# LM5116.net
KiCad netlist of a schematic drawn in Altium Designer
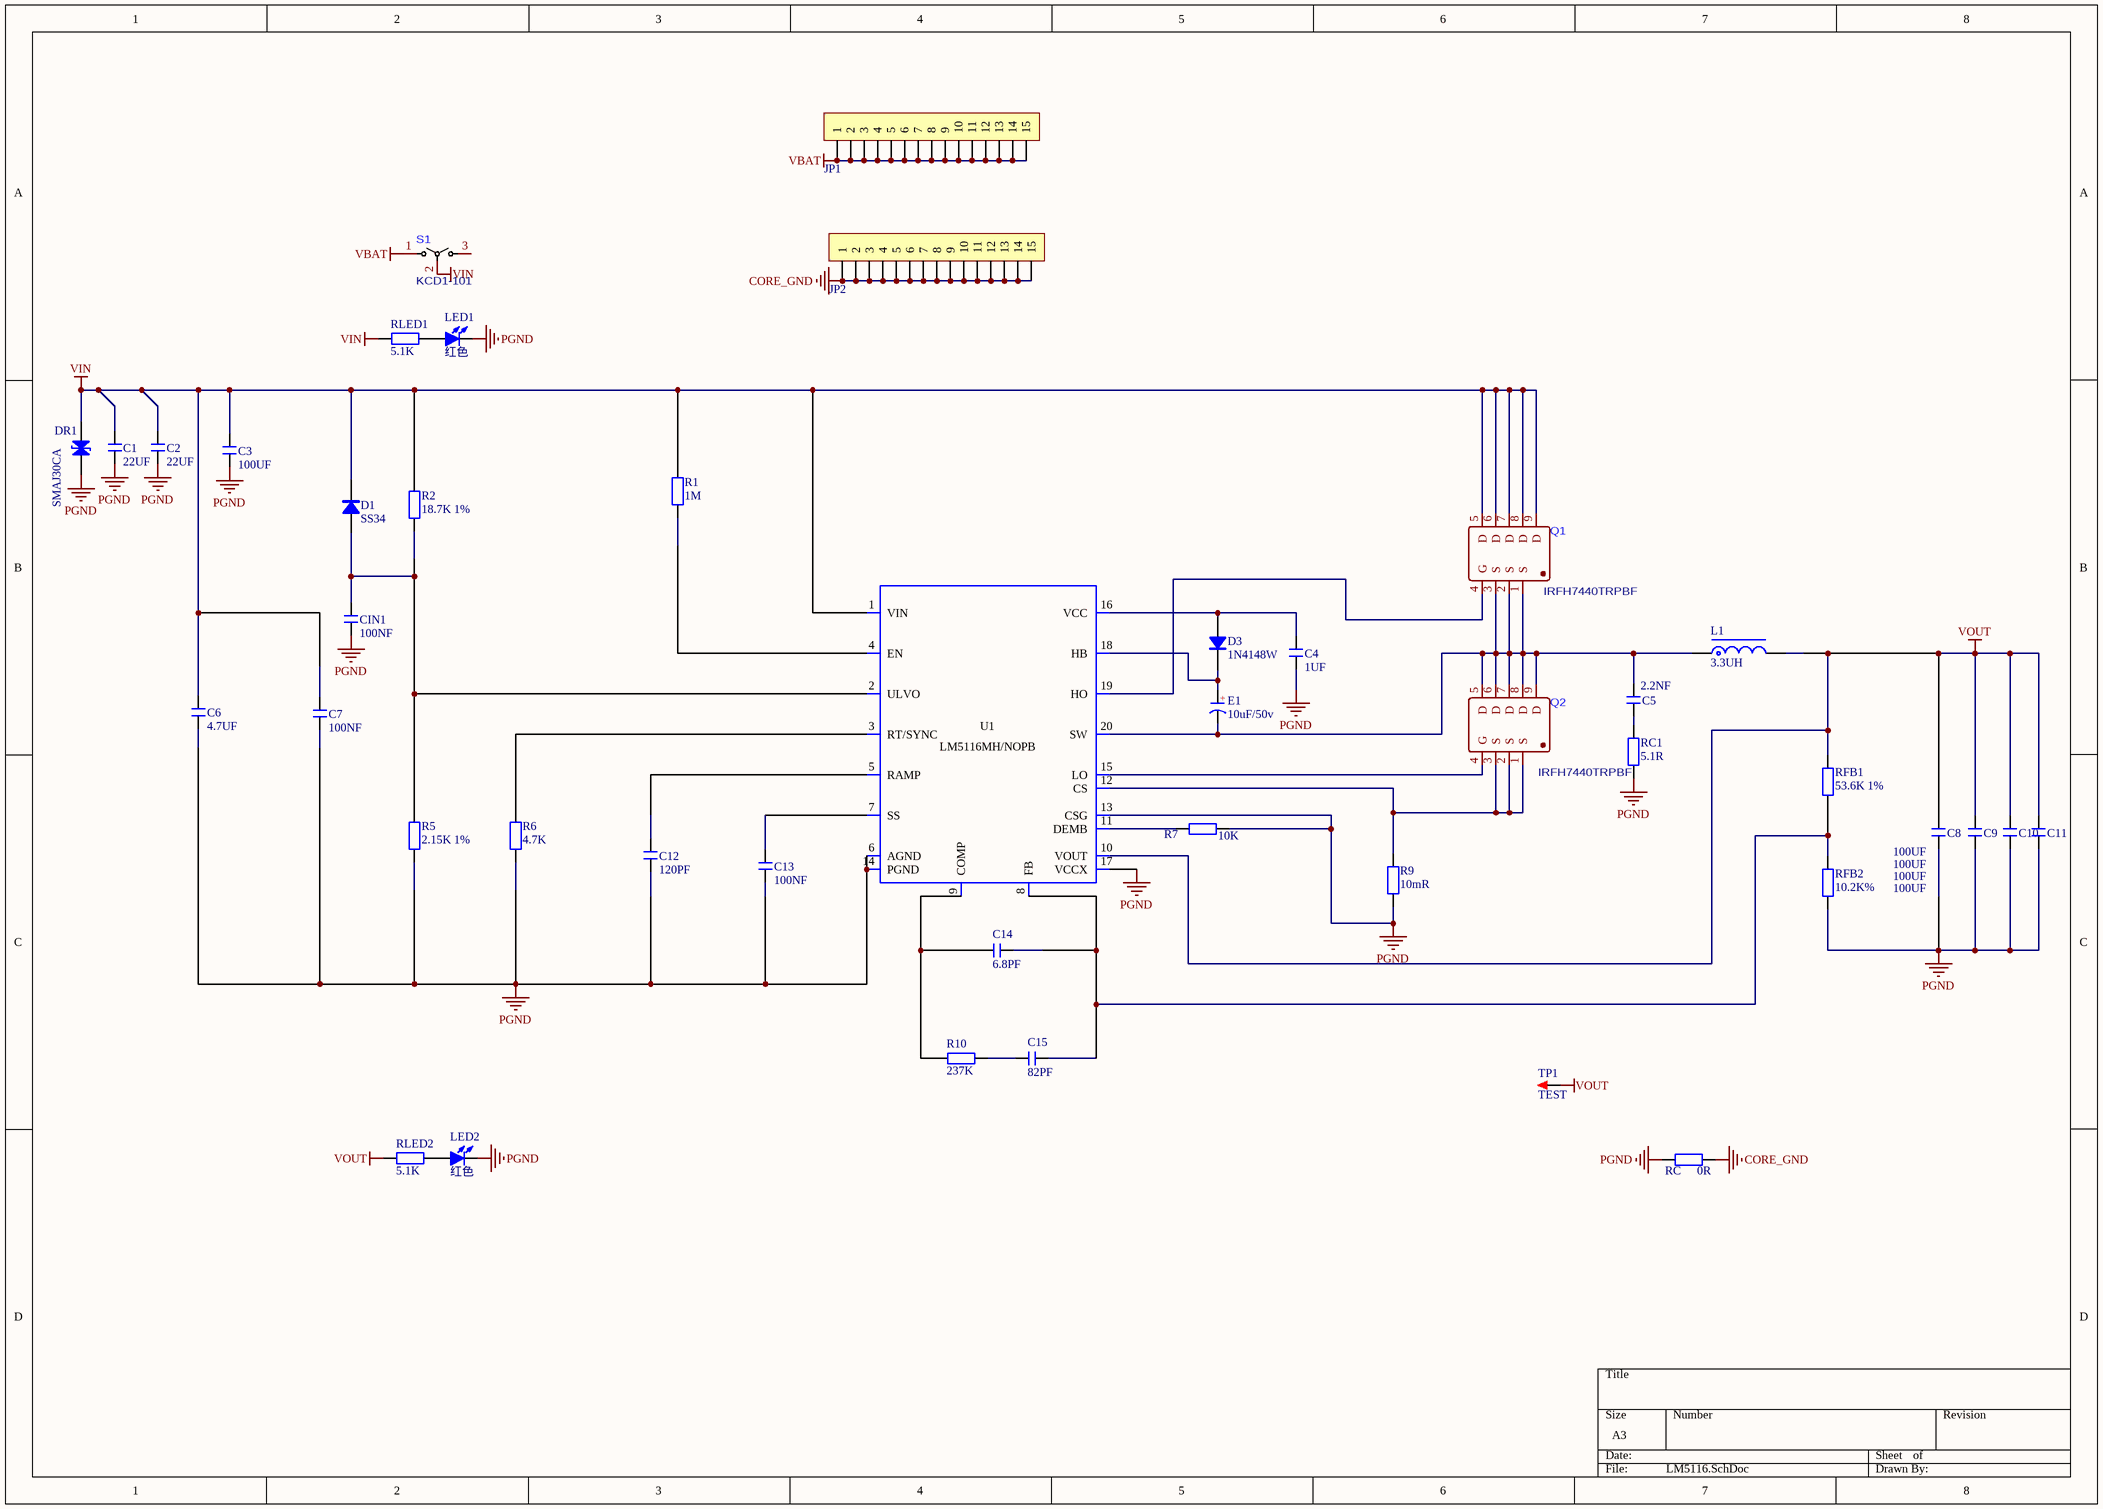
[diagram p0: LM5116.SchDoc]

(export (version "E")
  (design (tool "Eeschema 10.0.6"))
  (components
    (comp (ref "C1")
      (value "22UF")
      (footprint "C 1206_L")
      (description "无极性贴片电容")
      (fields (field (name "版权归属") "源创客"))
      (libsource (lib "3.1   - 电阻-电容-电感") (part "C"))
    )
    (comp (ref "C2")
      (value "22UF")
      (footprint "C 1206_L")
      (description "无极性贴片电容")
      (fields (field (name "版权归属") "源创客"))
      (libsource (lib "3.1   - 电阻-电容-电感") (part "C"))
    )
    (comp (ref "C3")
      (value "100UF")
      (footprint "C 1210_L")
      (description "无极性贴片电容")
      (fields (field (name "版权归属") "源创客"))
      (libsource (lib "3.1   - 电阻-电容-电感") (part "C"))
    )
    (comp (ref "C4")
      (value "1UF")
      (footprint "C 0805_L")
      (description "无极性贴片电容")
      (fields (field (name "版权归属") "源创客"))
      (libsource (lib "3.1   - 电阻-电容-电感") (part "C"))
    )
    (comp (ref "C5")
      (value "2.2NF")
      (footprint "C 0805_L")
      (description "无极性贴片电容")
      (fields (field (name "版权归属") "源创客"))
      (libsource (lib "3.1   - 电阻-电容-电感") (part "C"))
    )
    (comp (ref "C6")
      (value "4.7UF")
      (footprint "C 0805_L")
      (description "无极性贴片电容")
      (fields (field (name "版权归属") "源创客"))
      (libsource (lib "3.1   - 电阻-电容-电感") (part "C"))
    )
    (comp (ref "C7")
      (value "100NF")
      (footprint "C 0805_L")
      (description "无极性贴片电容")
      (fields (field (name "版权归属") "源创客"))
      (libsource (lib "3.1   - 电阻-电容-电感") (part "C"))
    )
    (comp (ref "C8")
      (value "100UF")
      (footprint "C 1210_L")
      (description "无极性贴片电容")
      (fields (field (name "版权归属") "源创客"))
      (libsource (lib "3.1   - 电阻-电容-电感") (part "C"))
    )
    (comp (ref "C9")
      (value "100UF")
      (footprint "C 1210_L")
      (description "无极性贴片电容")
      (fields (field (name "版权归属") "源创客"))
      (libsource (lib "3.1   - 电阻-电容-电感") (part "C"))
    )
    (comp (ref "C10")
      (value "100UF")
      (footprint "C 1210_L")
      (description "无极性贴片电容")
      (fields (field (name "版权归属") "源创客"))
      (libsource (lib "3.1   - 电阻-电容-电感") (part "C"))
    )
    (comp (ref "C11")
      (value "100UF")
      (footprint "C 1210_L")
      (description "无极性贴片电容")
      (fields (field (name "版权归属") "源创客"))
      (libsource (lib "3.1   - 电阻-电容-电感") (part "C"))
    )
    (comp (ref "C12")
      (value "120PF")
      (footprint "C 0805_L")
      (description "无极性贴片电容")
      (fields (field (name "版权归属") "源创客"))
      (libsource (lib "3.1   - 电阻-电容-电感") (part "C"))
    )
    (comp (ref "C13")
      (value "100NF")
      (footprint "C 0805_L")
      (description "无极性贴片电容")
      (fields (field (name "版权归属") "源创客"))
      (libsource (lib "3.1   - 电阻-电容-电感") (part "C"))
    )
    (comp (ref "C14")
      (value "6.8PF")
      (footprint "C 0805_L")
      (description "无极性贴片电容")
      (fields (field (name "版权归属") "源创客"))
      (libsource (lib "3.1   - 电阻-电容-电感") (part "C"))
    )
    (comp (ref "C15")
      (value "82PF")
      (footprint "C 0805_L")
      (description "无极性贴片电容")
      (fields (field (name "版权归属") "源创客"))
      (libsource (lib "3.1   - 电阻-电容-电感") (part "C"))
    )
    (comp (ref "CIN1")
      (value "100NF")
      (footprint "C 0805_L")
      (description "无极性贴片电容")
      (fields (field (name "版权归属") "源创客"))
      (libsource (lib "3.1   - 电阻-电容-电感") (part "C"))
    )
    (comp (ref "D1")
      (value "SS34")
      (footprint "SMA")
      (description "肖特基二极管")
      (fields (field (name "版权归属") "源创客"))
      (libsource (lib "8.1   - 二极管-整流桥") (part "SS34"))
    )
    (comp (ref "D3")
      (value "1N4148W")
      (footprint "SOD-123")
      (description "肖特基二极管")
      (fields (field (name "版权归属") "源创客"))
      (libsource (lib "8.1   - 二极管-整流桥") (part "SS34"))
    )
    (comp (ref "DR1")
      (value "SMAJ30CA")
      (footprint "SMA")
      (description "瞬态电压抑制二极管")
      (fields (field (name "版权归属") "源创客"))
      (libsource (lib "8.1   - 二极管-整流桥") (part "DR"))
    )
    (comp (ref "E1")
      (value "10uF/50v")
      (footprint "CAP 2.5*5*11-H")
      (description "直插电解电容")
      (fields (field (name "版权归属") "源创客"))
      (libsource (lib "3.1   - 电阻-电容-电感") (part "C-CAP"))
    )
    (comp (ref "JP1")
      (value "HDR-1X15")
      (footprint "HDR2.54-LI-15P")
      (description "15P接插件")
      (fields (field (name "版权归属") "源创客"))
      (libsource (lib "4.6   - 接插件-脚距2.54") (part "Header 15"))
    )
    (comp (ref "JP2")
      (value "HDR-1X15")
      (footprint "HDR2.54-LI-15P")
      (description "15P接插件")
      (fields (field (name "版权归属") "源创客"))
      (libsource (lib "4.6   - 接插件-脚距2.54") (part "Header 15"))
    )
    (comp (ref "L1")
      (value "3.3UH")
      (footprint "SMD-L-1770")
      (description "贴片功率电感")
      (fields (field (name "版权归属") "源创客"))
      (libsource (lib "3.1   - 电阻-电容-电感") (part "L-CD"))
    )
    (comp (ref "LED1")
      (value "红色")
      (footprint "LED 0805G")
      (description "贴片LED")
      (fields (field (name "版权归属") "源创客"))
      (libsource (lib "9.1   - LED") (part "LED-SMD"))
    )
    (comp (ref "LED2")
      (value "红色")
      (footprint "LED 0805G")
      (description "贴片LED")
      (fields (field (name "版权归属") "源创客"))
      (libsource (lib "9.1   - LED") (part "LED-SMD"))
    )
    (comp (ref "Q1")
      (value "IRFH7440TRPBF")
      (footprint "PQFN-8P_L5.8-W4.9-P1.27-LS6.0-BL")
      (libsource (lib "IRFH7440TRPBF") (part "IRFH7440TRPBF"))
    )
    (comp (ref "Q2")
      (value "IRFH7440TRPBF")
      (footprint "PQFN-8P_L5.8-W4.9-P1.27-LS6.0-BL")
      (libsource (lib "IRFH7440TRPBF") (part "IRFH7440TRPBF"))
    )
    (comp (ref "R1")
      (value "1M")
      (footprint "R 0805_L")
      (description "贴片电阻")
      (fields (field (name "版权归属") "源创客"))
      (libsource (lib "3.1   - 电阻-电容-电感") (part "R"))
    )
    (comp (ref "R2")
      (value "18.7K 1%")
      (footprint "R 0805_L")
      (description "贴片电阻")
      (fields (field (name "版权归属") "源创客"))
      (libsource (lib "3.1   - 电阻-电容-电感") (part "R"))
    )
    (comp (ref "R5")
      (value "2.15K 1%")
      (footprint "R 0805_L")
      (description "贴片电阻")
      (fields (field (name "版权归属") "源创客"))
      (libsource (lib "3.1   - 电阻-电容-电感") (part "R"))
    )
    (comp (ref "R6")
      (value "4.7K")
      (footprint "R 0805_L")
      (description "贴片电阻")
      (fields (field (name "版权归属") "源创客"))
      (libsource (lib "3.1   - 电阻-电容-电感") (part "R"))
    )
    (comp (ref "R7")
      (value "10K")
      (footprint "R 0805_L")
      (description "贴片电阻")
      (fields (field (name "版权归属") "源创客"))
      (libsource (lib "3.1   - 电阻-电容-电感") (part "R"))
    )
    (comp (ref "R9")
      (value "10mR")
      (footprint "R 1206_L")
      (description "贴片电阻")
      (fields (field (name "版权归属") "源创客"))
      (libsource (lib "3.1   - 电阻-电容-电感") (part "R"))
    )
    (comp (ref "R10")
      (value "237K")
      (footprint "R 0805_L")
      (description "贴片电阻")
      (fields (field (name "版权归属") "源创客"))
      (libsource (lib "3.1   - 电阻-电容-电感") (part "R"))
    )
    (comp (ref "RC")
      (value "0R")
      (footprint "R 0805_L")
      (description "贴片电阻")
      (fields (field (name "版权归属") "源创客"))
      (libsource (lib "3.1   - 电阻-电容-电感") (part "R"))
    )
    (comp (ref "RC1")
      (value "5.1R")
      (footprint "R 0805_L")
      (description "贴片电阻")
      (fields (field (name "版权归属") "源创客"))
      (libsource (lib "3.1   - 电阻-电容-电感") (part "R"))
    )
    (comp (ref "RFB1")
      (value "53.6K 1%")
      (footprint "R 0805_L")
      (description "贴片电阻")
      (fields (field (name "版权归属") "源创客"))
      (libsource (lib "3.1   - 电阻-电容-电感") (part "R"))
    )
    (comp (ref "RFB2")
      (value "10.2K%")
      (footprint "R 0805_L")
      (description "贴片电阻")
      (fields (field (name "版权归属") "源创客"))
      (libsource (lib "3.1   - 电阻-电容-电感") (part "R"))
    )
    (comp (ref "RLED1")
      (value "5.1K")
      (footprint "R 0805_L")
      (description "贴片电阻")
      (fields (field (name "版权归属") "源创客"))
      (libsource (lib "3.1   - 电阻-电容-电感") (part "R"))
    )
    (comp (ref "RLED2")
      (value "5.1K")
      (footprint "R 0805_L")
      (description "贴片电阻")
      (fields (field (name "版权归属") "源创客"))
      (libsource (lib "3.1   - 电阻-电容-电感") (part "R"))
    )
    (comp (ref "S1")
      (value "KCD1-101")
      (footprint "KEY-TH_CN-KCD1-101-3P")
      (libsource (lib "CN-KCD1-101-3P") (part "CN-KCD1-101-3P"))
    )
    (comp (ref "TP1")
      (value "TEST")
      (footprint "TEST 1.6")
      (description "测试点")
      (fields (field (name "版权归属") "源创客"))
      (libsource (lib "15.1 - 未分类器件") (part "TEST"))
    )
    (comp (ref "U1")
      (value "LM5116MH/NOPB")
      (footprint "HTSSOP-20_L6.5-W4.4-P0.65-LS6.4-BL-EP")
      (fields (field (name "PACKAGEREFERENCE") "LM5116MH/NOPB"))
      (libsource (lib "TI WEBENCH") (part "U1"))
    )
  )
  (nets
    (net (code "1") (name "CORE_GND") (class "Default")
      (node (ref "JP2") (pin "1") (pinfunction "1_1") (pintype "passive"))
      (node (ref "JP2") (pin "10") (pinfunction "10_10") (pintype "passive"))
      (node (ref "JP2") (pin "11") (pinfunction "11_11") (pintype "passive"))
      (node (ref "JP2") (pin "12") (pinfunction "12_12") (pintype "passive"))
      (node (ref "JP2") (pin "13") (pinfunction "13_13") (pintype "passive"))
      (node (ref "JP2") (pin "14") (pinfunction "14_14") (pintype "passive"))
      (node (ref "JP2") (pin "15") (pinfunction "15_15") (pintype "passive"))
      (node (ref "JP2") (pin "2") (pinfunction "2_2") (pintype "passive"))
      (node (ref "JP2") (pin "3") (pinfunction "3_3") (pintype "passive"))
      (node (ref "JP2") (pin "4") (pinfunction "4_4") (pintype "passive"))
      (node (ref "JP2") (pin "5") (pinfunction "5_5") (pintype "passive"))
      (node (ref "JP2") (pin "6") (pinfunction "6_6") (pintype "passive"))
      (node (ref "JP2") (pin "7") (pinfunction "7_7") (pintype "passive"))
      (node (ref "JP2") (pin "8") (pinfunction "8_8") (pintype "passive"))
      (node (ref "JP2") (pin "9") (pinfunction "9_9") (pintype "passive"))
      (node (ref "RC") (pin "1") (pinfunction "1_1") (pintype "passive"))
    )
    (net (code "2") (name "Net-(C5-Pad1)") (class "Default")
      (node (ref "C5") (pin "1") (pinfunction "1_1") (pintype "passive"))
      (node (ref "RC1") (pin "1") (pinfunction "1_1") (pintype "passive"))
    )
    (net (code "3") (name "Net-(C15-Pad1)") (class "Default")
      (node (ref "C15") (pin "1") (pinfunction "1_1") (pintype "passive"))
      (node (ref "R10") (pin "1") (pinfunction "1_1") (pintype "passive"))
    )
    (net (code "4") (name "Net-(D1-A)") (class "Default")
      (node (ref "CIN1") (pin "2") (pinfunction "2_2") (pintype "passive"))
      (node (ref "D1") (pin "1") (pinfunction "A_1") (pintype "passive"))
      (node (ref "R2") (pin "1") (pinfunction "1_1") (pintype "passive"))
      (node (ref "R5") (pin "2") (pinfunction "2_2") (pintype "passive"))
      (node (ref "U1") (pin "2") (pinfunction "ULVO_2") (pintype "passive"))
    )
    (net (code "5") (name "Net-(D3-A)") (class "Default")
      (node (ref "C4") (pin "2") (pinfunction "2_2") (pintype "passive"))
      (node (ref "D3") (pin "1") (pinfunction "A_1") (pintype "passive"))
      (node (ref "U1") (pin "16") (pinfunction "VCC_16") (pintype "passive"))
    )
    (net (code "6") (name "Net-(D3-K)") (class "Default")
      (node (ref "D3") (pin "2") (pinfunction "K_2") (pintype "passive"))
      (node (ref "E1") (pin "1") (pinfunction "A_1") (pintype "passive"))
      (node (ref "U1") (pin "18") (pinfunction "HB_18") (pintype "passive"))
    )
    (net (code "7") (name "Net-(E1-K)") (class "Default")
      (node (ref "C5") (pin "2") (pinfunction "2_2") (pintype "passive"))
      (node (ref "E1") (pin "2") (pinfunction "K_2") (pintype "passive"))
      (node (ref "L1") (pin "1") (pinfunction "1_1") (pintype "passive"))
      (node (ref "Q1") (pin "1") (pinfunction "S_1") (pintype "passive"))
      (node (ref "Q1") (pin "2") (pinfunction "S_2") (pintype "passive"))
      (node (ref "Q1") (pin "3") (pinfunction "S_3") (pintype "passive"))
      (node (ref "Q2") (pin "5") (pinfunction "D_5") (pintype "passive"))
      (node (ref "Q2") (pin "6") (pinfunction "D_6") (pintype "passive"))
      (node (ref "Q2") (pin "7") (pinfunction "D_7") (pintype "passive"))
      (node (ref "Q2") (pin "8") (pinfunction "D_8") (pintype "passive"))
      (node (ref "Q2") (pin "9") (pinfunction "D_9") (pintype "passive"))
      (node (ref "U1") (pin "20") (pinfunction "SW_20") (pintype "passive"))
    )
    (net (code "8") (name "Net-(LED1-A)") (class "Default")
      (node (ref "LED1") (pin "1") (pinfunction "A_1") (pintype "passive"))
      (node (ref "RLED1") (pin "1") (pinfunction "1_1") (pintype "passive"))
    )
    (net (code "9") (name "Net-(LED2-A)") (class "Default")
      (node (ref "LED2") (pin "1") (pinfunction "A_1") (pintype "passive"))
      (node (ref "RLED2") (pin "1") (pinfunction "1_1") (pintype "passive"))
    )
    (net (code "10") (name "Net-(Q1-G)") (class "Default")
      (node (ref "Q1") (pin "4") (pinfunction "G_4") (pintype "passive"))
      (node (ref "U1") (pin "19") (pinfunction "HO_19") (pintype "passive"))
    )
    (net (code "11") (name "Net-(Q2-G)") (class "Default")
      (node (ref "Q2") (pin "4") (pinfunction "G_4") (pintype "passive"))
      (node (ref "U1") (pin "15") (pinfunction "LO_15") (pintype "passive"))
    )
    (net (code "12") (name "Net-(U1-COMP)") (class "Default")
      (node (ref "C14") (pin "1") (pinfunction "1_1") (pintype "passive"))
      (node (ref "R10") (pin "2") (pinfunction "2_2") (pintype "passive"))
      (node (ref "U1") (pin "9") (pinfunction "COMP_9") (pintype "passive"))
    )
    (net (code "13") (name "Net-(U1-CS)") (class "Default")
      (node (ref "Q2") (pin "1") (pinfunction "S_1") (pintype "passive"))
      (node (ref "Q2") (pin "2") (pinfunction "S_2") (pintype "passive"))
      (node (ref "Q2") (pin "3") (pinfunction "S_3") (pintype "passive"))
      (node (ref "R9") (pin "2") (pinfunction "2_2") (pintype "passive"))
      (node (ref "U1") (pin "12") (pinfunction "CS_12") (pintype "passive"))
    )
    (net (code "14") (name "Net-(U1-DEMB)") (class "Default")
      (node (ref "R7") (pin "1") (pinfunction "1_1") (pintype "passive"))
      (node (ref "U1") (pin "11") (pinfunction "DEMB_11") (pintype "passive"))
    )
    (net (code "15") (name "Net-(U1-EN)") (class "Default")
      (node (ref "R1") (pin "1") (pinfunction "1_1") (pintype "passive"))
      (node (ref "U1") (pin "4") (pinfunction "EN_4") (pintype "passive"))
    )
    (net (code "16") (name "Net-(U1-FB)") (class "Default")
      (node (ref "C14") (pin "2") (pinfunction "2_2") (pintype "passive"))
      (node (ref "C15") (pin "2") (pinfunction "2_2") (pintype "passive"))
      (node (ref "RFB1") (pin "2") (pinfunction "2_2") (pintype "passive"))
      (node (ref "RFB2") (pin "1") (pinfunction "1_1") (pintype "passive"))
      (node (ref "U1") (pin "8") (pinfunction "FB_8") (pintype "passive"))
    )
    (net (code "17") (name "Net-(U1-RAMP)") (class "Default")
      (node (ref "C12") (pin "2") (pinfunction "2_2") (pintype "passive"))
      (node (ref "U1") (pin "5") (pinfunction "RAMP_5") (pintype "passive"))
    )
    (net (code "18") (name "Net-(U1-RT{slash}SYNC)") (class "Default")
      (node (ref "R6") (pin "2") (pinfunction "2_2") (pintype "passive"))
      (node (ref "U1") (pin "3") (pinfunction "RT/SYNC_3") (pintype "passive"))
    )
    (net (code "19") (name "Net-(U1-SS)") (class "Default")
      (node (ref "C13") (pin "2") (pinfunction "2_2") (pintype "passive"))
      (node (ref "U1") (pin "7") (pinfunction "SS_7") (pintype "passive"))
    )
    (net (code "20") (name "PGND") (class "Default")
      (node (ref "C1") (pin "1") (pinfunction "1_1") (pintype "passive"))
      (node (ref "C10") (pin "2") (pinfunction "2_2") (pintype "passive"))
      (node (ref "C11") (pin "2") (pinfunction "2_2") (pintype "passive"))
      (node (ref "C12") (pin "1") (pinfunction "1_1") (pintype "passive"))
      (node (ref "C13") (pin "1") (pinfunction "1_1") (pintype "passive"))
      (node (ref "C2") (pin "1") (pinfunction "1_1") (pintype "passive"))
      (node (ref "C3") (pin "1") (pinfunction "1_1") (pintype "passive"))
      (node (ref "C4") (pin "1") (pinfunction "1_1") (pintype "passive"))
      (node (ref "C6") (pin "1") (pinfunction "1_1") (pintype "passive"))
      (node (ref "C7") (pin "1") (pinfunction "1_1") (pintype "passive"))
      (node (ref "C8") (pin "2") (pinfunction "2_2") (pintype "passive"))
      (node (ref "C9") (pin "2") (pinfunction "2_2") (pintype "passive"))
      (node (ref "CIN1") (pin "1") (pinfunction "1_1") (pintype "passive"))
      (node (ref "DR1") (pin "2") (pinfunction "K_2") (pintype "passive"))
      (node (ref "LED1") (pin "2") (pinfunction "K_2") (pintype "passive"))
      (node (ref "LED2") (pin "2") (pinfunction "K_2") (pintype "passive"))
      (node (ref "R5") (pin "1") (pinfunction "1_1") (pintype "passive"))
      (node (ref "R6") (pin "1") (pinfunction "1_1") (pintype "passive"))
      (node (ref "R7") (pin "2") (pinfunction "2_2") (pintype "passive"))
      (node (ref "R9") (pin "1") (pinfunction "1_1") (pintype "passive"))
      (node (ref "RC") (pin "2") (pinfunction "2_2") (pintype "passive"))
      (node (ref "RC1") (pin "2") (pinfunction "2_2") (pintype "passive"))
      (node (ref "RFB2") (pin "2") (pinfunction "2_2") (pintype "passive"))
      (node (ref "U1") (pin "13") (pinfunction "CSG_13") (pintype "passive"))
      (node (ref "U1") (pin "14") (pinfunction "PGND_14") (pintype "passive"))
      (node (ref "U1") (pin "17") (pinfunction "VCCX_17") (pintype "passive"))
      (node (ref "U1") (pin "21") (pinfunction "EP_21") (pintype "passive"))
      (node (ref "U1") (pin "6") (pinfunction "AGND_6") (pintype "passive"))
    )
    (net (code "21") (name "VBAT") (class "Default")
      (node (ref "JP1") (pin "1") (pinfunction "1_1") (pintype "passive"))
      (node (ref "JP1") (pin "10") (pinfunction "10_10") (pintype "passive"))
      (node (ref "JP1") (pin "11") (pinfunction "11_11") (pintype "passive"))
      (node (ref "JP1") (pin "12") (pinfunction "12_12") (pintype "passive"))
      (node (ref "JP1") (pin "13") (pinfunction "13_13") (pintype "passive"))
      (node (ref "JP1") (pin "14") (pinfunction "14_14") (pintype "passive"))
      (node (ref "JP1") (pin "15") (pinfunction "15_15") (pintype "passive"))
      (node (ref "JP1") (pin "2") (pinfunction "2_2") (pintype "passive"))
      (node (ref "JP1") (pin "3") (pinfunction "3_3") (pintype "passive"))
      (node (ref "JP1") (pin "4") (pinfunction "4_4") (pintype "passive"))
      (node (ref "JP1") (pin "5") (pinfunction "5_5") (pintype "passive"))
      (node (ref "JP1") (pin "6") (pinfunction "6_6") (pintype "passive"))
      (node (ref "JP1") (pin "7") (pinfunction "7_7") (pintype "passive"))
      (node (ref "JP1") (pin "8") (pinfunction "8_8") (pintype "passive"))
      (node (ref "JP1") (pin "9") (pinfunction "9_9") (pintype "passive"))
      (node (ref "S1") (pin "1") (pinfunction "1_1") (pintype "passive"))
    )
    (net (code "22") (name "VIN") (class "Default")
      (node (ref "C1") (pin "2") (pinfunction "2_2") (pintype "passive"))
      (node (ref "C2") (pin "2") (pinfunction "2_2") (pintype "passive"))
      (node (ref "C3") (pin "2") (pinfunction "2_2") (pintype "passive"))
      (node (ref "C6") (pin "2") (pinfunction "2_2") (pintype "passive"))
      (node (ref "C7") (pin "2") (pinfunction "2_2") (pintype "passive"))
      (node (ref "D1") (pin "2") (pinfunction "K_2") (pintype "passive"))
      (node (ref "DR1") (pin "1") (pinfunction "A_1") (pintype "passive"))
      (node (ref "Q1") (pin "5") (pinfunction "D_5") (pintype "passive"))
      (node (ref "Q1") (pin "6") (pinfunction "D_6") (pintype "passive"))
      (node (ref "Q1") (pin "7") (pinfunction "D_7") (pintype "passive"))
      (node (ref "Q1") (pin "8") (pinfunction "D_8") (pintype "passive"))
      (node (ref "Q1") (pin "9") (pinfunction "D_9") (pintype "passive"))
      (node (ref "R1") (pin "2") (pinfunction "2_2") (pintype "passive"))
      (node (ref "R2") (pin "2") (pinfunction "2_2") (pintype "passive"))
      (node (ref "RLED1") (pin "2") (pinfunction "2_2") (pintype "passive"))
      (node (ref "S1") (pin "2") (pinfunction "2_2") (pintype "passive"))
      (node (ref "U1") (pin "1") (pinfunction "VIN_1") (pintype "passive"))
    )
    (net (code "23") (name "VOUT") (class "Default")
      (node (ref "C10") (pin "1") (pinfunction "1_1") (pintype "passive"))
      (node (ref "C11") (pin "1") (pinfunction "1_1") (pintype "passive"))
      (node (ref "C8") (pin "1") (pinfunction "1_1") (pintype "passive"))
      (node (ref "C9") (pin "1") (pinfunction "1_1") (pintype "passive"))
      (node (ref "L1") (pin "2") (pinfunction "2_2") (pintype "passive"))
      (node (ref "RFB1") (pin "1") (pinfunction "1_1") (pintype "passive"))
      (node (ref "RLED2") (pin "2") (pinfunction "2_2") (pintype "passive"))
      (node (ref "TP1") (pin "1") (pinfunction "1_1") (pintype "passive"))
      (node (ref "U1") (pin "10") (pinfunction "VOUT_10") (pintype "passive"))
    )
    (net (code "24") (name "unconnected-(S1-Pad3)") (class "Default")
      (node (ref "S1") (pin "3") (pinfunction "3_3") (pintype "passive"))
    )
  )
)
